# pam2803-boost-driver-17mm-mk-1_0.net
KiCad netlist of a schematic drawn in EAGLE
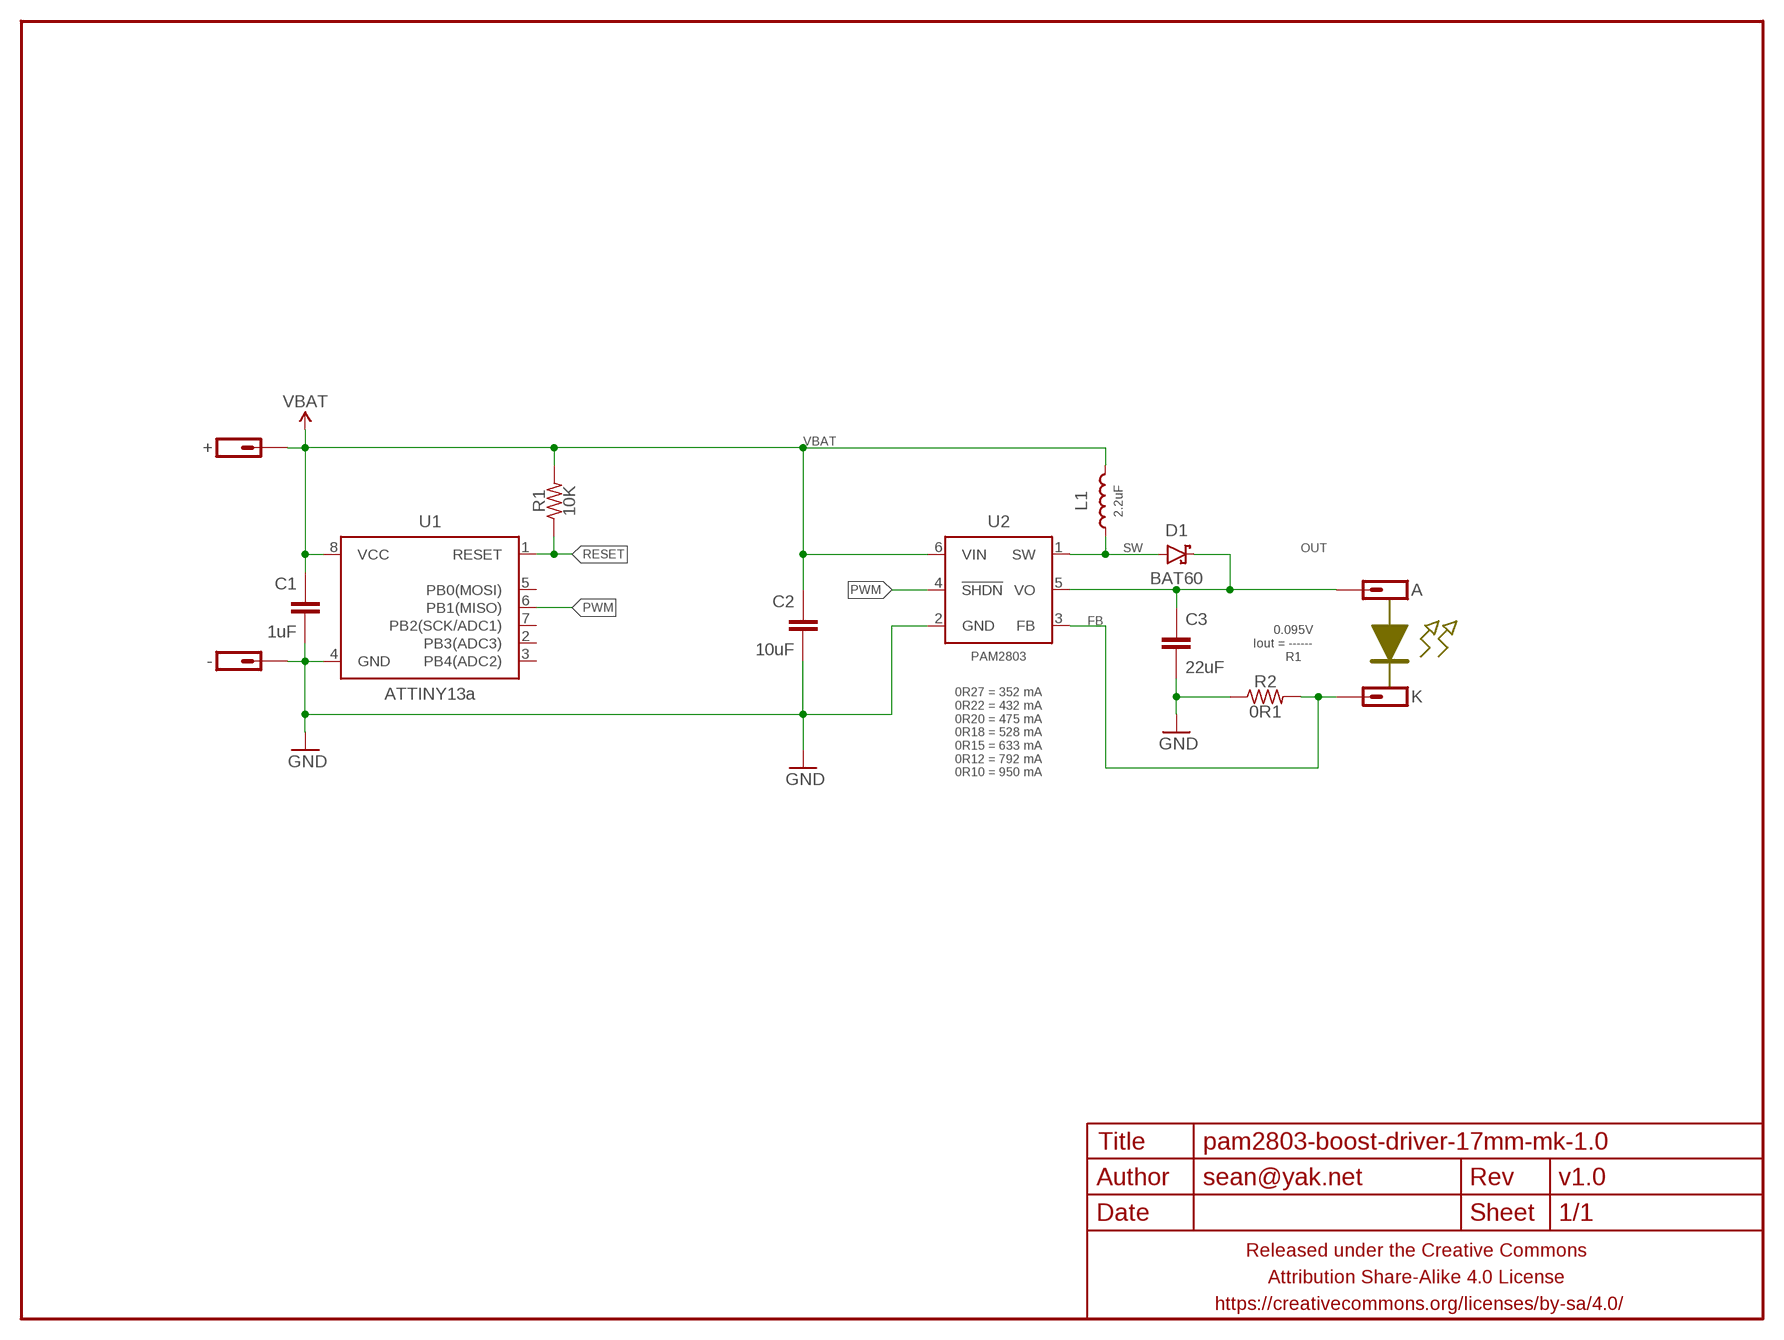
[diagram p0: schematic, sheet 1]

(export (version "E")
  (design (tool "Eeschema 10.0.6"))
  (components
    (comp (ref "+")
      (value "M01PTH-1MM-CIR-NS")
      (footprint "eagle-import:1X01-1MM-CIR-NS")
      (libsource (lib "eagle-import") (part "M01PTH-1MM-CIR-NS"))
    )
    (comp (ref "-")
      (value "M01NOT-A-VIA-NOPE")
      (footprint "eagle-import:1X01_NOSILK_NOSTOP")
      (libsource (lib "eagle-import") (part "M01NOT-A-VIA-NOPE"))
    )
    (comp (ref "A")
      (value "M01SMD-1.75DIA")
      (footprint "eagle-import:1X01-SMD-1.75DIA")
      (libsource (lib "eagle-import") (part "M01SMD-1.75DIA"))
    )
    (comp (ref "C1")
      (value "1uF")
      (footprint "eagle-import:C0603-TIGHTER")
      (libsource (lib "eagle-import") (part "CAPACITOR-CERAMICC0603-TIGHTER"))
    )
    (comp (ref "C2")
      (value "10uF")
      (footprint "eagle-import:C0805-TIGHTER")
      (libsource (lib "eagle-import") (part "CAPACITOR-CERAMICC0805-TIGHTER"))
    )
    (comp (ref "C3")
      (value "22uF")
      (footprint "eagle-import:C0805-TIGHTER")
      (libsource (lib "eagle-import") (part "CAPACITOR-CERAMICC0805-TIGHTER"))
    )
    (comp (ref "D1")
      (value "BAT60")
      (footprint "eagle-import:SOD323-SCHOTTKY")
      (libsource (lib "eagle-import") (part "DIODE-SCHOTTKYSOD323"))
    )
    (comp (ref "FRAME1")
      (value "FRAME-LETTERNO_PACKAGE")
      (footprint "eagle-import:DUMMY")
      (fields (field (name "DESIGNER") "sean@yak.net") (field (name "VERSION") "v1.0"))
      (libsource (lib "eagle-import") (part "FRAME-LETTERNO_PACKAGE"))
    )
    (comp (ref "K")
      (value "M01SMD-1.75DIA")
      (footprint "eagle-import:1X01-SMD-1.75DIA")
      (libsource (lib "eagle-import") (part "M01SMD-1.75DIA"))
    )
    (comp (ref "L1")
      (value "2.2uF")
      (footprint "eagle-import:XFL4020")
      (libsource (lib "eagle-import") (part "INDUCTORXFL4020"))
    )
    (comp (ref "R1")
      (value "10K")
      (footprint "eagle-import:R0603-TIGHTER")
      (libsource (lib "eagle-import") (part "RESISTORR0603-TIGHTER"))
    )
    (comp (ref "R2")
      (value "0R1")
      (footprint "eagle-import:R0805-TIGHTER")
      (libsource (lib "eagle-import") (part "RESISTORR0805-TIGHTER"))
    )
    (comp (ref "U1")
      (value "ATTINY13a")
      (footprint "eagle-import:SO08-SKINNYPADS")
      (libsource (lib "eagle-import") (part "ATTINY13SOIC-NARROWER"))
    )
    (comp (ref "U2")
      (value "PAM2803")
      (footprint "eagle-import:SOT23-6")
      (libsource (lib "eagle-import") (part "PAM2803SOT23-6"))
    )
  )
  (nets
    (net (code "1") (name "/FB") (class "Default")
      (node (ref "K") (pin "P$1") (pinfunction "1_P$1") (pintype "passive"))
      (node (ref "R2") (pin "2") (pinfunction "2_2") (pintype "passive"))
      (node (ref "U2") (pin "3") (pinfunction "FB_3") (pintype "bidirectional"))
    )
    (net (code "2") (name "/OUT") (class "Default")
      (node (ref "A") (pin "P$1") (pinfunction "1_P$1") (pintype "passive"))
      (node (ref "C3") (pin "1") (pinfunction "1_1") (pintype "passive"))
      (node (ref "D1") (pin "C") (pinfunction "C_C") (pintype "passive"))
      (node (ref "U2") (pin "5") (pinfunction "VO_5") (pintype "bidirectional"))
    )
    (net (code "3") (name "/SW") (class "Default")
      (node (ref "D1") (pin "A") (pinfunction "A_A") (pintype "passive"))
      (node (ref "L1") (pin "P$2") (pinfunction "2_P$2") (pintype "passive"))
      (node (ref "U2") (pin "1") (pinfunction "SW_1") (pintype "bidirectional"))
    )
    (net (code "4") (name "GND") (class "Default")
      (node (ref "-") (pin "P$1") (pinfunction "1_P$1") (pintype "passive"))
      (node (ref "C1") (pin "2") (pinfunction "2_2") (pintype "passive"))
      (node (ref "C2") (pin "2") (pinfunction "2_2") (pintype "passive"))
      (node (ref "C3") (pin "2") (pinfunction "2_2") (pintype "passive"))
      (node (ref "R2") (pin "1") (pinfunction "1_1") (pintype "passive"))
      (node (ref "U1") (pin "4") (pinfunction "GND_4") (pintype "bidirectional"))
      (node (ref "U2") (pin "2") (pinfunction "GND_2") (pintype "bidirectional"))
    )
    (net (code "5") (name "PWM") (class "Default")
      (node (ref "U1") (pin "6") (pinfunction "PB1(MISO)_6") (pintype "bidirectional"))
      (node (ref "U2") (pin "4") (pinfunction "~{SHDN}_4") (pintype "bidirectional"))
    )
    (net (code "6") (name "RESET") (class "Default")
      (node (ref "R1") (pin "1") (pinfunction "1_1") (pintype "passive"))
      (node (ref "U1") (pin "1") (pinfunction "RESET_1") (pintype "bidirectional"))
    )
    (net (code "7") (name "VBAT") (class "Default")
      (node (ref "+") (pin "1") (pinfunction "1_1") (pintype "passive"))
      (node (ref "C1") (pin "1") (pinfunction "1_1") (pintype "passive"))
      (node (ref "C2") (pin "1") (pinfunction "1_1") (pintype "passive"))
      (node (ref "L1") (pin "P$1") (pinfunction "1_P$1") (pintype "passive"))
      (node (ref "R1") (pin "2") (pinfunction "2_2") (pintype "passive"))
      (node (ref "U1") (pin "8") (pinfunction "VCC_8") (pintype "bidirectional"))
      (node (ref "U2") (pin "6") (pinfunction "VIN_6") (pintype "bidirectional"))
    )
    (net (code "8") (name "unconnected-(U1-PB0(MOSI)-Pad5)") (class "Default")
      (node (ref "U1") (pin "5") (pinfunction "PB0(MOSI)_5") (pintype "bidirectional"))
    )
    (net (code "9") (name "unconnected-(U1-PB2(SCK{slash}ADC1)-Pad7)") (class "Default")
      (node (ref "U1") (pin "7") (pinfunction "PB2(SCK/ADC1)_7") (pintype "bidirectional"))
    )
    (net (code "10") (name "unconnected-(U1-PB3(ADC3)-Pad2)") (class "Default")
      (node (ref "U1") (pin "2") (pinfunction "PB3(ADC3)_2") (pintype "bidirectional"))
    )
    (net (code "11") (name "unconnected-(U1-PB4(ADC2)-Pad3)") (class "Default")
      (node (ref "U1") (pin "3") (pinfunction "PB4(ADC2)_3") (pintype "bidirectional"))
    )
  )
)
